# Tugas_Day_0-_Teresia_Rosa_Savera_Putri.net
KiCad netlist of a schematic drawn in EAGLE
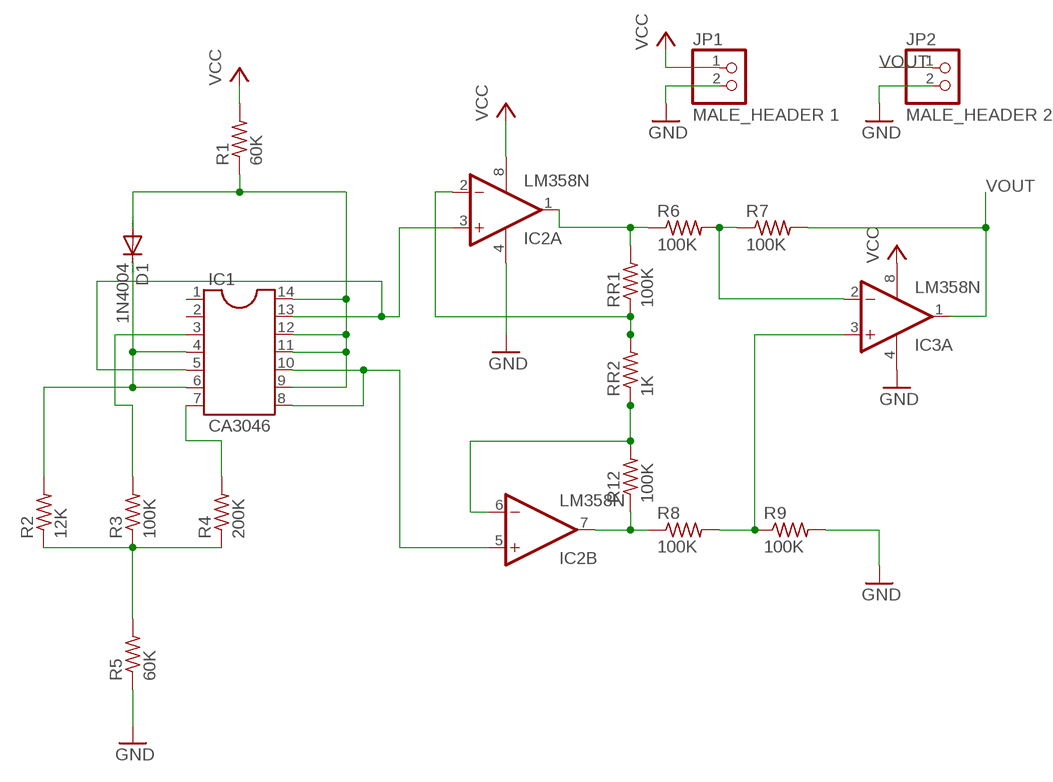
[diagram p0: schematic, sheet 1]

(export (version "E")
  (design (tool "Eeschema 10.0.6"))
  (components
    (comp (ref "D1")
      (value "1N4004")
      (footprint "eagle-import:DO41-10")
      (libsource (lib "eagle-import") (part "1N4004"))
    )
    (comp (ref "IC1")
      (value "CA3046")
      (footprint "eagle-import:DIL14")
      (libsource (lib "eagle-import") (part "DIL14"))
    )
    (comp (ref "IC2")
      (value "LM358N")
      (footprint "eagle-import:DIL08")
      (libsource (lib "eagle-import") (part "LM358N"))
    )
    (comp (ref "IC3")
      (value "LM358N")
      (footprint "eagle-import:DIL08")
      (libsource (lib "eagle-import") (part "LM358N"))
    )
    (comp (ref "JP1")
      (value "MALE_HEADER 1")
      (footprint "eagle-import:1X02")
      (libsource (lib "eagle-import") (part "PINHD-1X2"))
    )
    (comp (ref "JP2")
      (value "MALE_HEADER 2")
      (footprint "eagle-import:1X02")
      (libsource (lib "eagle-import") (part "PINHD-1X2"))
    )
    (comp (ref "R1")
      (value "60K")
      (footprint "eagle-import:0204_7")
      (libsource (lib "eagle-import") (part "R-US_0204/7"))
    )
    (comp (ref "R2")
      (value "12K")
      (footprint "eagle-import:0204_7")
      (libsource (lib "eagle-import") (part "R-US_0204/7"))
    )
    (comp (ref "R3")
      (value "100K")
      (footprint "eagle-import:0204_7")
      (libsource (lib "eagle-import") (part "R-US_0204/7"))
    )
    (comp (ref "R4")
      (value "200K")
      (footprint "eagle-import:0204_7")
      (libsource (lib "eagle-import") (part "R-US_0204/7"))
    )
    (comp (ref "R5")
      (value "60K")
      (footprint "eagle-import:0204_7")
      (libsource (lib "eagle-import") (part "R-US_0204/7"))
    )
    (comp (ref "R6")
      (value "100K")
      (footprint "eagle-import:0204_7")
      (libsource (lib "eagle-import") (part "R-US_0204/7"))
    )
    (comp (ref "R7")
      (value "100K")
      (footprint "eagle-import:0204_7")
      (libsource (lib "eagle-import") (part "R-US_0204/7"))
    )
    (comp (ref "R8")
      (value "100K")
      (footprint "eagle-import:0204_7")
      (libsource (lib "eagle-import") (part "R-US_0204/7"))
    )
    (comp (ref "R9")
      (value "100K")
      (footprint "eagle-import:0204_7")
      (libsource (lib "eagle-import") (part "R-US_0204/7"))
    )
    (comp (ref "R12")
      (value "100K")
      (footprint "eagle-import:0204_7")
      (libsource (lib "eagle-import") (part "R-US_0204/7"))
    )
    (comp (ref "RR1")
      (value "100K")
      (footprint "eagle-import:0204_7")
      (libsource (lib "eagle-import") (part "R-US_0204/7"))
    )
    (comp (ref "RR2")
      (value "1K")
      (footprint "eagle-import:0204_7")
      (libsource (lib "eagle-import") (part "R-US_0204/7"))
    )
  )
  (nets
    (net (code "1") (name "/VOUT") (class "Default")
      (node (ref "IC3") (pin "1") (pinfunction "OUT_1") (pintype "output"))
      (node (ref "JP2") (pin "1") (pinfunction "1_1") (pintype "passive"))
      (node (ref "R7") (pin "2") (pinfunction "2_2") (pintype "passive"))
    )
    (net (code "2") (name "GND") (class "Default")
      (node (ref "IC2") (pin "4") (pinfunction "V-_4") (pintype "power_in"))
      (node (ref "IC3") (pin "4") (pinfunction "V-_4") (pintype "power_in"))
      (node (ref "JP1") (pin "2") (pinfunction "2_2") (pintype "passive"))
      (node (ref "JP2") (pin "2") (pinfunction "2_2") (pintype "passive"))
      (node (ref "R5") (pin "1") (pinfunction "1_1") (pintype "passive"))
      (node (ref "R9") (pin "2") (pinfunction "2_2") (pintype "passive"))
    )
    (net (code "3") (name "Net-(D1-PadA)") (class "Default")
      (node (ref "D1") (pin "A") (pinfunction "A_A") (pintype "passive"))
      (node (ref "IC1") (pin "11") (pinfunction "11_11") (pintype "passive"))
      (node (ref "IC1") (pin "12") (pinfunction "12_12") (pintype "passive"))
      (node (ref "IC1") (pin "14") (pinfunction "14_14") (pintype "passive"))
      (node (ref "IC1") (pin "9") (pinfunction "9_9") (pintype "passive"))
      (node (ref "R1") (pin "1") (pinfunction "1_1") (pintype "passive"))
    )
    (net (code "4") (name "Net-(D1-PadC)") (class "Default")
      (node (ref "D1") (pin "C") (pinfunction "C_C") (pintype "passive"))
      (node (ref "IC1") (pin "4") (pinfunction "4_4") (pintype "passive"))
      (node (ref "IC1") (pin "6") (pinfunction "6_6") (pintype "passive"))
      (node (ref "R2") (pin "2") (pinfunction "2_2") (pintype "passive"))
    )
    (net (code "5") (name "Net-(IC1-Pad3)") (class "Default")
      (node (ref "IC1") (pin "3") (pinfunction "3_3") (pintype "passive"))
      (node (ref "R3") (pin "2") (pinfunction "2_2") (pintype "passive"))
    )
    (net (code "6") (name "Net-(IC1-Pad7)") (class "Default")
      (node (ref "IC1") (pin "7") (pinfunction "7_7") (pintype "passive"))
      (node (ref "R4") (pin "2") (pinfunction "2_2") (pintype "passive"))
    )
    (net (code "7") (name "Net-(IC2A-+IN)") (class "Default")
      (node (ref "IC1") (pin "13") (pinfunction "13_13") (pintype "passive"))
      (node (ref "IC1") (pin "5") (pinfunction "5_5") (pintype "passive"))
      (node (ref "IC2") (pin "3") (pinfunction "+IN_3") (pintype "input"))
    )
    (net (code "8") (name "Net-(IC2A--IN)") (class "Default")
      (node (ref "IC2") (pin "2") (pinfunction "-IN_2") (pintype "input"))
      (node (ref "RR1") (pin "1") (pinfunction "1_1") (pintype "passive"))
      (node (ref "RR2") (pin "2") (pinfunction "2_2") (pintype "passive"))
    )
    (net (code "9") (name "Net-(IC2A-OUT)") (class "Default")
      (node (ref "IC2") (pin "1") (pinfunction "OUT_1") (pintype "output"))
      (node (ref "R6") (pin "1") (pinfunction "1_1") (pintype "passive"))
      (node (ref "RR1") (pin "2") (pinfunction "2_2") (pintype "passive"))
    )
    (net (code "10") (name "Net-(IC2B-+IN)") (class "Default")
      (node (ref "IC1") (pin "10") (pinfunction "10_10") (pintype "passive"))
      (node (ref "IC1") (pin "8") (pinfunction "8_8") (pintype "passive"))
      (node (ref "IC2") (pin "5") (pinfunction "+IN_5") (pintype "input"))
    )
    (net (code "11") (name "Net-(IC2B--IN)") (class "Default")
      (node (ref "IC2") (pin "6") (pinfunction "-IN_6") (pintype "input"))
      (node (ref "R12") (pin "2") (pinfunction "2_2") (pintype "passive"))
      (node (ref "RR2") (pin "1") (pinfunction "1_1") (pintype "passive"))
    )
    (net (code "12") (name "Net-(IC2B-OUT)") (class "Default")
      (node (ref "IC2") (pin "7") (pinfunction "OUT_7") (pintype "output"))
      (node (ref "R12") (pin "1") (pinfunction "1_1") (pintype "passive"))
      (node (ref "R8") (pin "1") (pinfunction "1_1") (pintype "passive"))
    )
    (net (code "13") (name "Net-(IC3A-+IN)") (class "Default")
      (node (ref "IC3") (pin "3") (pinfunction "+IN_3") (pintype "input"))
      (node (ref "R8") (pin "2") (pinfunction "2_2") (pintype "passive"))
      (node (ref "R9") (pin "1") (pinfunction "1_1") (pintype "passive"))
    )
    (net (code "14") (name "Net-(IC3A--IN)") (class "Default")
      (node (ref "IC3") (pin "2") (pinfunction "-IN_2") (pintype "input"))
      (node (ref "R6") (pin "2") (pinfunction "2_2") (pintype "passive"))
      (node (ref "R7") (pin "1") (pinfunction "1_1") (pintype "passive"))
    )
    (net (code "15") (name "Net-(R2-Pad1)") (class "Default")
      (node (ref "R2") (pin "1") (pinfunction "1_1") (pintype "passive"))
      (node (ref "R3") (pin "1") (pinfunction "1_1") (pintype "passive"))
      (node (ref "R4") (pin "1") (pinfunction "1_1") (pintype "passive"))
      (node (ref "R5") (pin "2") (pinfunction "2_2") (pintype "passive"))
    )
    (net (code "16") (name "VCC") (class "Default")
      (node (ref "IC2") (pin "8") (pinfunction "V+_8") (pintype "power_in"))
      (node (ref "IC3") (pin "8") (pinfunction "V+_8") (pintype "power_in"))
      (node (ref "JP1") (pin "1") (pinfunction "1_1") (pintype "passive"))
      (node (ref "R1") (pin "2") (pinfunction "2_2") (pintype "passive"))
    )
    (net (code "17") (name "unconnected-(IC1-Pad1)") (class "Default")
      (node (ref "IC1") (pin "1") (pinfunction "1_1") (pintype "passive"))
    )
    (net (code "18") (name "unconnected-(IC1-Pad2)") (class "Default")
      (node (ref "IC1") (pin "2") (pinfunction "2_2") (pintype "passive"))
    )
  )
)
